# MBUS_reader_through_hole.net
KiCad netlist of a schematic drawn in EAGLE
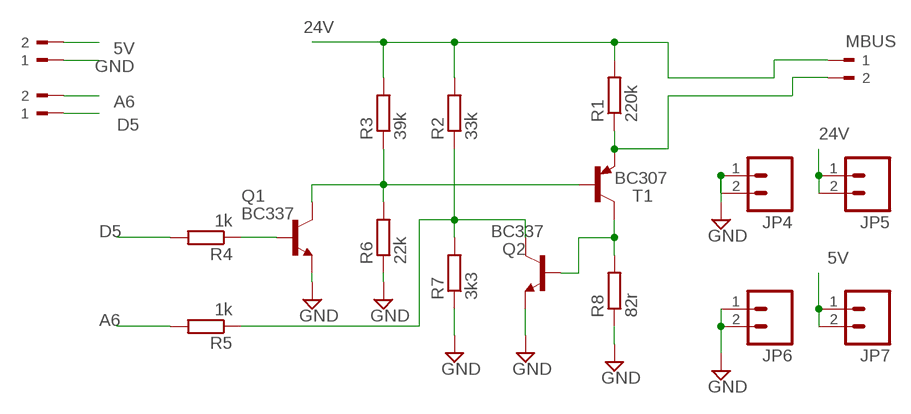
[diagram p0: schematic, sheet 1]

(export (version "E")
  (design (tool "Eeschema 10.0.6"))
  (components
    (comp (ref "JP4")
      (value "M02PTH")
      (footprint "eagle-import:1X02")
      (libsource (lib "eagle-import") (part "M02PTH"))
    )
    (comp (ref "JP5")
      (value "M02PTH")
      (footprint "eagle-import:1X02")
      (libsource (lib "eagle-import") (part "M02PTH"))
    )
    (comp (ref "JP6")
      (value "M02PTH")
      (footprint "eagle-import:1X02")
      (libsource (lib "eagle-import") (part "M02PTH"))
    )
    (comp (ref "JP7")
      (value "M02PTH")
      (footprint "eagle-import:1X02")
      (libsource (lib "eagle-import") (part "M02PTH"))
    )
    (comp (ref "MBUS")
      (value "180-2")
      (footprint "eagle-import:180-2")
      (libsource (lib "eagle-import") (part "180-2"))
    )
    (comp (ref "MBUS1")
      (value "180-2")
      (footprint "eagle-import:180-2")
      (libsource (lib "eagle-import") (part "180-2"))
    )
    (comp (ref "MBUS2")
      (value "180-2")
      (footprint "eagle-import:180-2")
      (libsource (lib "eagle-import") (part "180-2"))
    )
    (comp (ref "Q1")
      (value "BC337")
      (footprint "eagle-import:TO92")
      (libsource (lib "eagle-import") (part "BC337"))
    )
    (comp (ref "Q2")
      (value "BC337")
      (footprint "eagle-import:TO92")
      (libsource (lib "eagle-import") (part "BC337"))
    )
    (comp (ref "R1")
      (value "220k")
      (footprint "eagle-import:0204_7")
      (libsource (lib "eagle-import") (part "R-EU_0204/7"))
    )
    (comp (ref "R2")
      (value "33k")
      (footprint "eagle-import:0204_7")
      (libsource (lib "eagle-import") (part "R-EU_0204/7"))
    )
    (comp (ref "R3")
      (value "39k")
      (footprint "eagle-import:0204_7")
      (libsource (lib "eagle-import") (part "R-EU_0204/7"))
    )
    (comp (ref "R4")
      (value "1k")
      (footprint "eagle-import:0204_7")
      (libsource (lib "eagle-import") (part "R-EU_0204/7"))
    )
    (comp (ref "R5")
      (value "1k")
      (footprint "eagle-import:0204_7")
      (libsource (lib "eagle-import") (part "R-EU_0204/7"))
    )
    (comp (ref "R6")
      (value "22k")
      (footprint "eagle-import:0204_7")
      (libsource (lib "eagle-import") (part "R-EU_0204/7"))
    )
    (comp (ref "R7")
      (value "3k3")
      (footprint "eagle-import:0204_7")
      (libsource (lib "eagle-import") (part "R-EU_0204/7"))
    )
    (comp (ref "R8")
      (value "82r")
      (footprint "eagle-import:0204_7")
      (libsource (lib "eagle-import") (part "R-EU_0204/7"))
    )
    (comp (ref "T1")
      (value "BC307")
      (footprint "eagle-import:TO92")
      (libsource (lib "eagle-import") (part "BC307"))
    )
  )
  (nets
    (net (code "1") (name "/5V") (class "Default")
      (node (ref "JP7") (pin "1") (pinfunction "1_1") (pintype "passive"))
      (node (ref "JP7") (pin "2") (pinfunction "2_2") (pintype "passive"))
      (node (ref "MBUS2") (pin "2") (pinfunction "2_2") (pintype "passive"))
    )
    (net (code "2") (name "/24V") (class "Default")
      (node (ref "JP5") (pin "1") (pinfunction "1_1") (pintype "passive"))
      (node (ref "JP5") (pin "2") (pinfunction "2_2") (pintype "passive"))
      (node (ref "MBUS") (pin "1") (pinfunction "1_1") (pintype "passive"))
      (node (ref "R1") (pin "2") (pinfunction "2_2") (pintype "passive"))
      (node (ref "R2") (pin "2") (pinfunction "2_2") (pintype "passive"))
      (node (ref "R3") (pin "2") (pinfunction "2_2") (pintype "passive"))
    )
    (net (code "3") (name "/A6") (class "Default")
      (node (ref "MBUS1") (pin "2") (pinfunction "2_2") (pintype "passive"))
      (node (ref "R5") (pin "2") (pinfunction "2_2") (pintype "passive"))
    )
    (net (code "4") (name "/D5") (class "Default")
      (node (ref "MBUS1") (pin "1") (pinfunction "1_1") (pintype "passive"))
      (node (ref "R4") (pin "2") (pinfunction "2_2") (pintype "passive"))
    )
    (net (code "5") (name "GND") (class "Default")
      (node (ref "JP4") (pin "1") (pinfunction "1_1") (pintype "passive"))
      (node (ref "JP4") (pin "2") (pinfunction "2_2") (pintype "passive"))
      (node (ref "JP6") (pin "1") (pinfunction "1_1") (pintype "passive"))
      (node (ref "JP6") (pin "2") (pinfunction "2_2") (pintype "passive"))
      (node (ref "MBUS2") (pin "1") (pinfunction "1_1") (pintype "passive"))
      (node (ref "Q1") (pin "1") (pinfunction "E_1") (pintype "passive"))
      (node (ref "Q2") (pin "1") (pinfunction "E_1") (pintype "passive"))
      (node (ref "R6") (pin "1") (pinfunction "1_1") (pintype "passive"))
      (node (ref "R7") (pin "1") (pinfunction "1_1") (pintype "passive"))
      (node (ref "R8") (pin "1") (pinfunction "1_1") (pintype "passive"))
    )
    (net (code "6") (name "Net-(Q1-B)") (class "Default")
      (node (ref "Q1") (pin "2") (pinfunction "B_2") (pintype "passive"))
      (node (ref "R4") (pin "1") (pinfunction "1_1") (pintype "passive"))
    )
    (net (code "7") (name "Net-(Q1-C)") (class "Default")
      (node (ref "Q1") (pin "3") (pinfunction "C_3") (pintype "passive"))
      (node (ref "R3") (pin "1") (pinfunction "1_1") (pintype "passive"))
      (node (ref "R6") (pin "2") (pinfunction "2_2") (pintype "passive"))
      (node (ref "T1") (pin "2") (pinfunction "B_2") (pintype "passive"))
    )
    (net (code "8") (name "Net-(Q2-B)") (class "Default")
      (node (ref "Q2") (pin "2") (pinfunction "B_2") (pintype "passive"))
      (node (ref "R8") (pin "2") (pinfunction "2_2") (pintype "passive"))
      (node (ref "T1") (pin "3") (pinfunction "C_3") (pintype "passive"))
    )
    (net (code "9") (name "Net-(Q2-C)") (class "Default")
      (node (ref "Q2") (pin "3") (pinfunction "C_3") (pintype "passive"))
      (node (ref "R2") (pin "1") (pinfunction "1_1") (pintype "passive"))
      (node (ref "R5") (pin "1") (pinfunction "1_1") (pintype "passive"))
      (node (ref "R7") (pin "2") (pinfunction "2_2") (pintype "passive"))
    )
    (net (code "10") (name "Net-(T1-E)") (class "Default")
      (node (ref "MBUS") (pin "2") (pinfunction "2_2") (pintype "passive"))
      (node (ref "R1") (pin "1") (pinfunction "1_1") (pintype "passive"))
      (node (ref "T1") (pin "1") (pinfunction "E_1") (pintype "passive"))
    )
  )
)
